# 8-electrovalvulas_V3.net
KiCad netlist of a schematic drawn in EAGLE
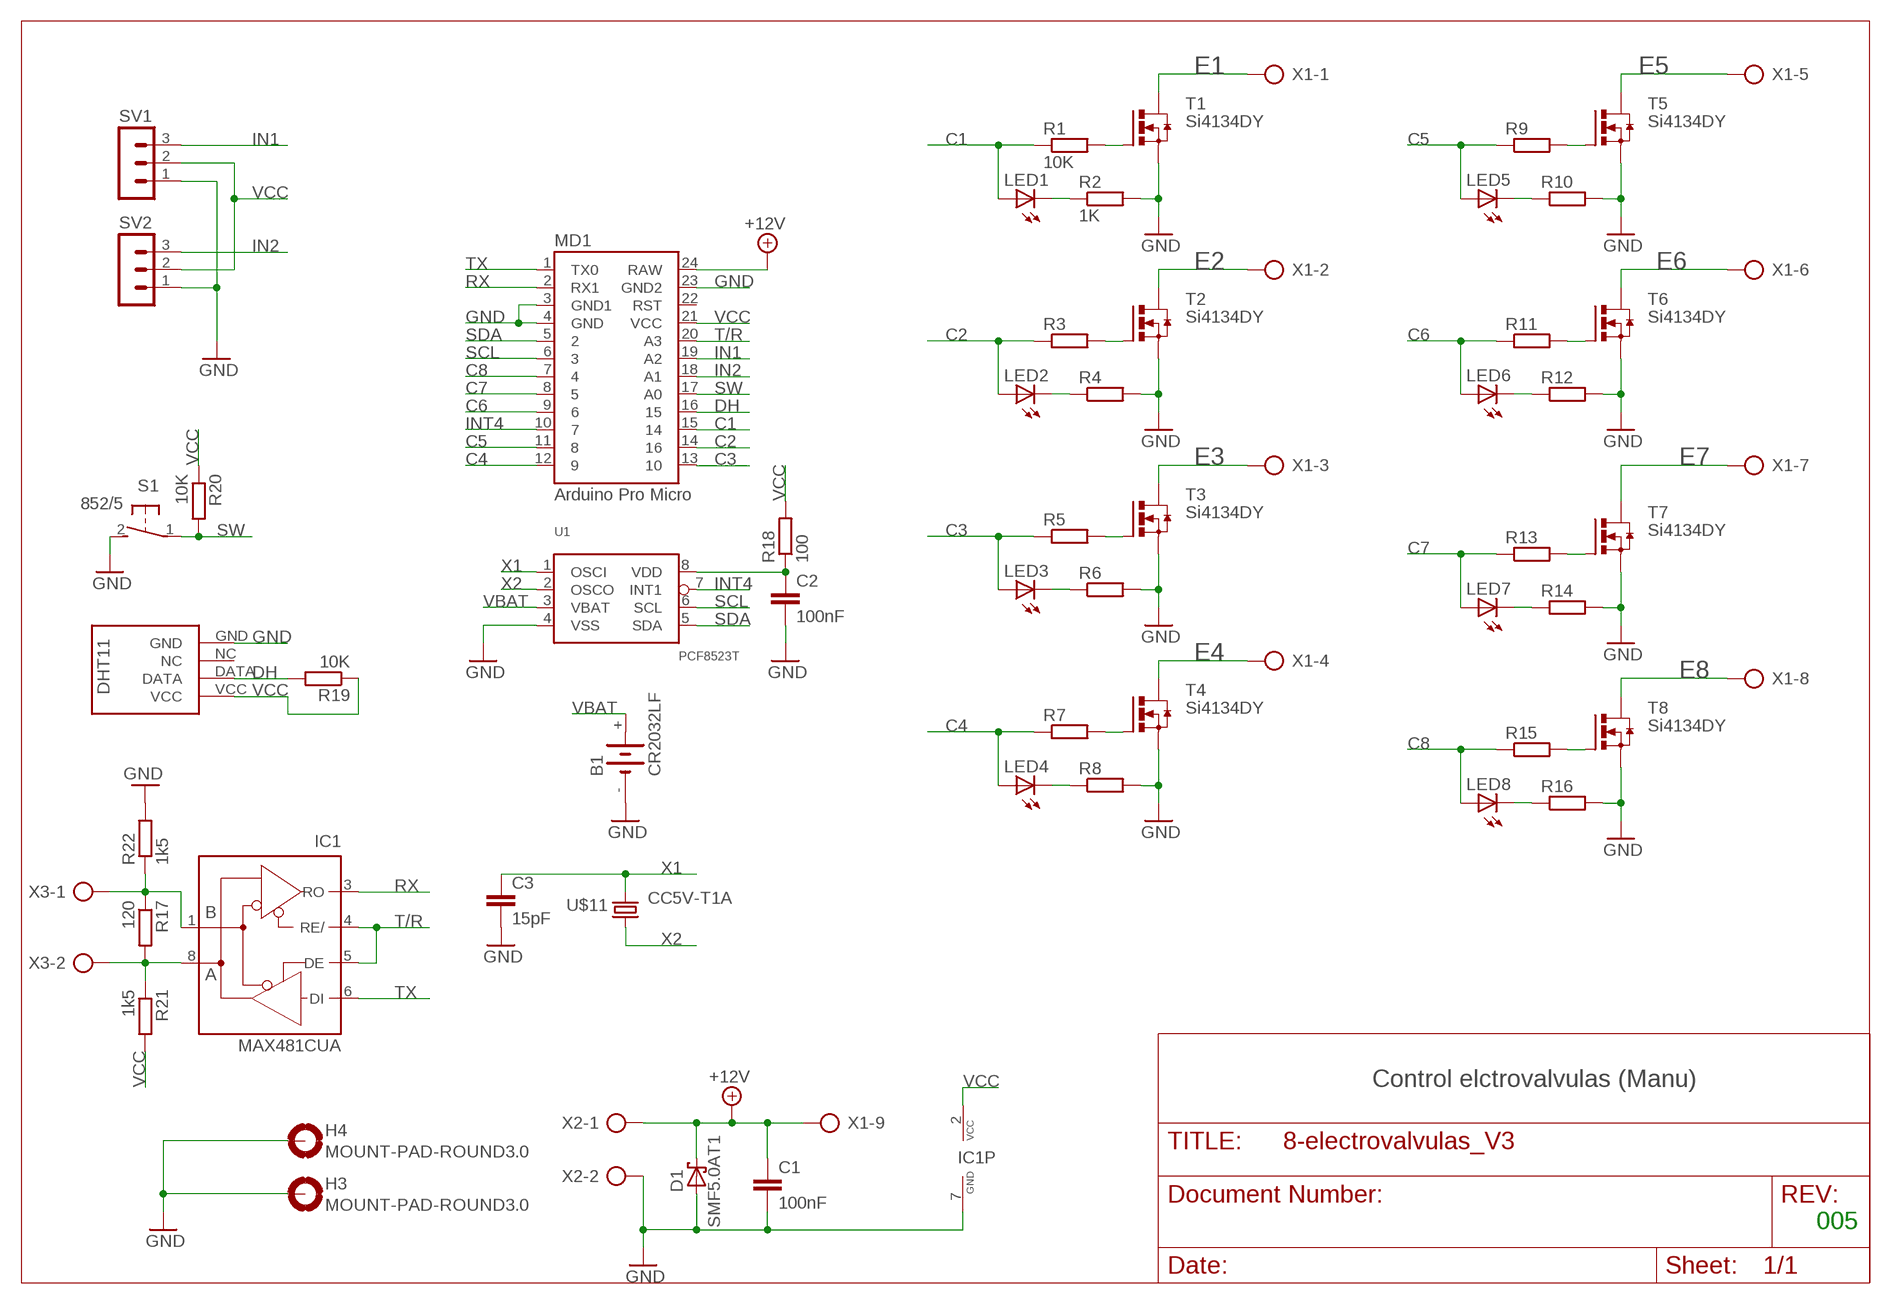
[diagram p0: schematic, sheet 1]

(export (version "E")
  (design (tool "Eeschema 10.0.6"))
  (components
    (comp (ref "B1")
      (value "CR2032LF")
      (footprint "eagle-import:BATTERY_1236_C")
      (libsource (lib "eagle-import") (part "BATTERY_2032LF"))
    )
    (comp (ref "C1")
      (value "100nF")
      (footprint "eagle-import:C1206")
      (libsource (lib "eagle-import") (part "C-EUC1206"))
    )
    (comp (ref "C2")
      (value "100nF")
      (footprint "eagle-import:C0603")
      (libsource (lib "eagle-import") (part "C-EUC0603"))
    )
    (comp (ref "C3")
      (value "15pF")
      (footprint "eagle-import:C0603")
      (libsource (lib "eagle-import") (part "C-EUC0603"))
    )
    (comp (ref "D1")
      (value "SMF5.0AT1")
      (footprint "eagle-import:SOD123FL")
      (libsource (lib "eagle-import") (part "SMF5.0AT1"))
    )
    (comp (ref "H3")
      (value "MOUNT-PAD-ROUND3.0")
      (footprint "eagle-import:3,0-PAD")
      (libsource (lib "eagle-import") (part "MOUNT-PAD-ROUND3.0"))
    )
    (comp (ref "H4")
      (value "MOUNT-PAD-ROUND3.0")
      (footprint "eagle-import:3,0-PAD")
      (libsource (lib "eagle-import") (part "MOUNT-PAD-ROUND3.0"))
    )
    (comp (ref "IC1")
      (value "MAX481CUA")
      (footprint "eagle-import:UMAX8")
      (fields (field (name "MPN") "MAX481CUA+"))
      (libsource (lib "eagle-import") (part "MAX481CUA"))
    )
    (comp (ref "IC10")
      (value "DHT11-PION.")
      (footprint "eagle-import:DHT11-PION.")
      (libsource (lib "eagle-import") (part "DHT11-PION."))
    )
    (comp (ref "LED1")
      (value "LEDSML0805")
      (footprint "eagle-import:SML0805")
      (libsource (lib "eagle-import") (part "LEDSML0805"))
    )
    (comp (ref "LED2")
      (value "LEDSML0805")
      (footprint "eagle-import:SML0805")
      (libsource (lib "eagle-import") (part "LEDSML0805"))
    )
    (comp (ref "LED3")
      (value "LEDSML0805")
      (footprint "eagle-import:SML0805")
      (libsource (lib "eagle-import") (part "LEDSML0805"))
    )
    (comp (ref "LED4")
      (value "LEDSML0805")
      (footprint "eagle-import:SML0805")
      (libsource (lib "eagle-import") (part "LEDSML0805"))
    )
    (comp (ref "LED5")
      (value "LEDSML0805")
      (footprint "eagle-import:SML0805")
      (libsource (lib "eagle-import") (part "LEDSML0805"))
    )
    (comp (ref "LED6")
      (value "LEDSML0805")
      (footprint "eagle-import:SML0805")
      (libsource (lib "eagle-import") (part "LEDSML0805"))
    )
    (comp (ref "LED7")
      (value "LEDSML0805")
      (footprint "eagle-import:SML0805")
      (libsource (lib "eagle-import") (part "LEDSML0805"))
    )
    (comp (ref "LED8")
      (value "LEDSML0805")
      (footprint "eagle-import:SML0805")
      (libsource (lib "eagle-import") (part "LEDSML0805"))
    )
    (comp (ref "MD1")
      (value "Arduino Pro Micro")
      (footprint "eagle-import:PRO_MICRO")
      (libsource (lib "eagle-import") (part "PRO_MICRO"))
    )
    (comp (ref "R1")
      (value "10K")
      (footprint "eagle-import:R0603")
      (libsource (lib "eagle-import") (part "R-EU_R0603"))
    )
    (comp (ref "R2")
      (value "1K")
      (footprint "eagle-import:R0603")
      (libsource (lib "eagle-import") (part "R-EU_R0603"))
    )
    (comp (ref "R3")
      (value "R-EU_R0603")
      (footprint "eagle-import:R0603")
      (libsource (lib "eagle-import") (part "R-EU_R0603"))
    )
    (comp (ref "R4")
      (value "R-EU_R0603")
      (footprint "eagle-import:R0603")
      (libsource (lib "eagle-import") (part "R-EU_R0603"))
    )
    (comp (ref "R5")
      (value "R-EU_R0603")
      (footprint "eagle-import:R0603")
      (libsource (lib "eagle-import") (part "R-EU_R0603"))
    )
    (comp (ref "R6")
      (value "R-EU_R0603")
      (footprint "eagle-import:R0603")
      (libsource (lib "eagle-import") (part "R-EU_R0603"))
    )
    (comp (ref "R7")
      (value "R-EU_R0603")
      (footprint "eagle-import:R0603")
      (libsource (lib "eagle-import") (part "R-EU_R0603"))
    )
    (comp (ref "R8")
      (value "R-EU_R0603")
      (footprint "eagle-import:R0603")
      (libsource (lib "eagle-import") (part "R-EU_R0603"))
    )
    (comp (ref "R9")
      (value "R-EU_R0603")
      (footprint "eagle-import:R0603")
      (libsource (lib "eagle-import") (part "R-EU_R0603"))
    )
    (comp (ref "R10")
      (value "R-EU_R0603")
      (footprint "eagle-import:R0603")
      (libsource (lib "eagle-import") (part "R-EU_R0603"))
    )
    (comp (ref "R11")
      (value "R-EU_R0603")
      (footprint "eagle-import:R0603")
      (libsource (lib "eagle-import") (part "R-EU_R0603"))
    )
    (comp (ref "R12")
      (value "R-EU_R0603")
      (footprint "eagle-import:R0603")
      (libsource (lib "eagle-import") (part "R-EU_R0603"))
    )
    (comp (ref "R13")
      (value "R-EU_R0603")
      (footprint "eagle-import:R0603")
      (libsource (lib "eagle-import") (part "R-EU_R0603"))
    )
    (comp (ref "R14")
      (value "R-EU_R0603")
      (footprint "eagle-import:R0603")
      (libsource (lib "eagle-import") (part "R-EU_R0603"))
    )
    (comp (ref "R15")
      (value "R-EU_R0603")
      (footprint "eagle-import:R0603")
      (libsource (lib "eagle-import") (part "R-EU_R0603"))
    )
    (comp (ref "R16")
      (value "R-EU_R0603")
      (footprint "eagle-import:R0603")
      (libsource (lib "eagle-import") (part "R-EU_R0603"))
    )
    (comp (ref "R17")
      (value "120")
      (footprint "eagle-import:R0603")
      (libsource (lib "eagle-import") (part "R-EU_R0603"))
    )
    (comp (ref "R18")
      (value "100")
      (footprint "eagle-import:R0603")
      (libsource (lib "eagle-import") (part "R-EU_R0603"))
    )
    (comp (ref "R19")
      (value "10K")
      (footprint "eagle-import:R0603")
      (libsource (lib "eagle-import") (part "R-EU_R0603"))
    )
    (comp (ref "R20")
      (value "10K")
      (footprint "eagle-import:R0603")
      (libsource (lib "eagle-import") (part "R-EU_R0603"))
    )
    (comp (ref "R21")
      (value "1k5")
      (footprint "eagle-import:R0603")
      (libsource (lib "eagle-import") (part "R-EU_R0603"))
    )
    (comp (ref "R22")
      (value "1k5")
      (footprint "eagle-import:R0603")
      (libsource (lib "eagle-import") (part "R-EU_R0603"))
    )
    (comp (ref "S1")
      (value "852/5")
      (footprint "eagle-import:B3F-31XX")
      (libsource (lib "eagle-import") (part "31-XX"))
    )
    (comp (ref "SV1")
      (value "MA03-1")
      (footprint "eagle-import:MA03-1")
      (libsource (lib "eagle-import") (part "MA03-1"))
    )
    (comp (ref "SV2")
      (value "MA03-1")
      (footprint "eagle-import:MA03-1")
      (libsource (lib "eagle-import") (part "MA03-1"))
    )
    (comp (ref "T1")
      (value "Si4134DY")
      (footprint "eagle-import:SO-08")
      (libsource (lib "eagle-import") (part "SI4134DY"))
    )
    (comp (ref "T2")
      (value "Si4134DY")
      (footprint "eagle-import:SO-08")
      (libsource (lib "eagle-import") (part "SI4134DY"))
    )
    (comp (ref "T3")
      (value "Si4134DY")
      (footprint "eagle-import:SO-08")
      (libsource (lib "eagle-import") (part "SI4134DY"))
    )
    (comp (ref "T4")
      (value "Si4134DY")
      (footprint "eagle-import:SO-08")
      (libsource (lib "eagle-import") (part "SI4134DY"))
    )
    (comp (ref "T5")
      (value "Si4134DY")
      (footprint "eagle-import:SO-08")
      (libsource (lib "eagle-import") (part "SI4134DY"))
    )
    (comp (ref "T6")
      (value "Si4134DY")
      (footprint "eagle-import:SO-08")
      (libsource (lib "eagle-import") (part "SI4134DY"))
    )
    (comp (ref "T7")
      (value "Si4134DY")
      (footprint "eagle-import:SO-08")
      (libsource (lib "eagle-import") (part "SI4134DY"))
    )
    (comp (ref "T8")
      (value "Si4134DY")
      (footprint "eagle-import:SO-08")
      (libsource (lib "eagle-import") (part "SI4134DY"))
    )
    (comp (ref "U$11")
      (value "CC5V-T1A")
      (footprint "eagle-import:T1A")
      (libsource (lib "eagle-import") (part "CC5V-T1A"))
    )
    (comp (ref "U1")
      (value "PCF8523T")
      (footprint "eagle-import:SOT96-1")
      (libsource (lib "eagle-import") (part "PCF8523T"))
    )
    (comp (ref "X1")
      (value "AK300/9")
      (footprint "eagle-import:AK300_9")
      (libsource (lib "eagle-import") (part "AK300/9"))
    )
    (comp (ref "X2")
      (value "AK300/2")
      (footprint "eagle-import:AK300_2")
      (libsource (lib "eagle-import") (part "AK300/2"))
    )
    (comp (ref "X3")
      (value "AK300/2")
      (footprint "eagle-import:AK300_2")
      (libsource (lib "eagle-import") (part "AK300/2"))
    )
  )
  (nets
    (net (code "1") (name "+12V") (class "Default")
      (node (ref "C1") (pin "1") (pinfunction "1_1") (pintype "passive"))
      (node (ref "D1") (pin "C") (pinfunction "C_C") (pintype "passive"))
      (node (ref "MD1") (pin "24") (pinfunction "RAW_24") (pintype "bidirectional"))
      (node (ref "X1") (pin "9") (pinfunction "KL_9") (pintype "passive"))
      (node (ref "X2") (pin "1") (pinfunction "KL_1") (pintype "passive"))
    )
    (net (code "2") (name "/C1") (class "Default")
      (node (ref "LED1") (pin "A") (pinfunction "A_A") (pintype "passive"))
      (node (ref "MD1") (pin "15") (pinfunction "14_15") (pintype "bidirectional"))
      (node (ref "R1") (pin "1") (pinfunction "1_1") (pintype "passive"))
    )
    (net (code "3") (name "/C2") (class "Default")
      (node (ref "LED2") (pin "A") (pinfunction "A_A") (pintype "passive"))
      (node (ref "MD1") (pin "14") (pinfunction "16_14") (pintype "bidirectional"))
      (node (ref "R3") (pin "1") (pinfunction "1_1") (pintype "passive"))
    )
    (net (code "4") (name "/C3") (class "Default")
      (node (ref "LED3") (pin "A") (pinfunction "A_A") (pintype "passive"))
      (node (ref "MD1") (pin "13") (pinfunction "10_13") (pintype "bidirectional"))
      (node (ref "R5") (pin "1") (pinfunction "1_1") (pintype "passive"))
    )
    (net (code "5") (name "/C4") (class "Default")
      (node (ref "LED4") (pin "A") (pinfunction "A_A") (pintype "passive"))
      (node (ref "MD1") (pin "12") (pinfunction "9_12") (pintype "bidirectional"))
      (node (ref "R7") (pin "1") (pinfunction "1_1") (pintype "passive"))
    )
    (net (code "6") (name "/C5") (class "Default")
      (node (ref "LED5") (pin "A") (pinfunction "A_A") (pintype "passive"))
      (node (ref "MD1") (pin "11") (pinfunction "8_11") (pintype "bidirectional"))
      (node (ref "R9") (pin "1") (pinfunction "1_1") (pintype "passive"))
    )
    (net (code "7") (name "/C6") (class "Default")
      (node (ref "LED6") (pin "A") (pinfunction "A_A") (pintype "passive"))
      (node (ref "MD1") (pin "9") (pinfunction "6_9") (pintype "bidirectional"))
      (node (ref "R11") (pin "1") (pinfunction "1_1") (pintype "passive"))
    )
    (net (code "8") (name "/C7") (class "Default")
      (node (ref "LED7") (pin "A") (pinfunction "A_A") (pintype "passive"))
      (node (ref "MD1") (pin "8") (pinfunction "5_8") (pintype "bidirectional"))
      (node (ref "R13") (pin "1") (pinfunction "1_1") (pintype "passive"))
    )
    (net (code "9") (name "/C8") (class "Default")
      (node (ref "LED8") (pin "A") (pinfunction "A_A") (pintype "passive"))
      (node (ref "MD1") (pin "7") (pinfunction "4_7") (pintype "bidirectional"))
      (node (ref "R15") (pin "1") (pinfunction "1_1") (pintype "passive"))
    )
    (net (code "10") (name "/DH") (class "Default")
      (node (ref "IC10") (pin "DATA") (pinfunction "DATA_DATA") (pintype "bidirectional"))
      (node (ref "MD1") (pin "16") (pinfunction "15_16") (pintype "bidirectional"))
      (node (ref "R19") (pin "2") (pinfunction "2_2") (pintype "passive"))
    )
    (net (code "11") (name "/E1") (class "Default")
      (node (ref "T1") (pin "5") (pinfunction "D_5") (pintype "passive"))
      (node (ref "T1") (pin "6") (pinfunction "D_6") (pintype "passive"))
      (node (ref "T1") (pin "7") (pinfunction "D_7") (pintype "passive"))
      (node (ref "T1") (pin "8") (pinfunction "D_8") (pintype "passive"))
      (node (ref "X1") (pin "1") (pinfunction "KL_1") (pintype "passive"))
    )
    (net (code "12") (name "/E2") (class "Default")
      (node (ref "T2") (pin "5") (pinfunction "D_5") (pintype "passive"))
      (node (ref "T2") (pin "6") (pinfunction "D_6") (pintype "passive"))
      (node (ref "T2") (pin "7") (pinfunction "D_7") (pintype "passive"))
      (node (ref "T2") (pin "8") (pinfunction "D_8") (pintype "passive"))
      (node (ref "X1") (pin "2") (pinfunction "KL_2") (pintype "passive"))
    )
    (net (code "13") (name "/E3") (class "Default")
      (node (ref "T3") (pin "5") (pinfunction "D_5") (pintype "passive"))
      (node (ref "T3") (pin "6") (pinfunction "D_6") (pintype "passive"))
      (node (ref "T3") (pin "7") (pinfunction "D_7") (pintype "passive"))
      (node (ref "T3") (pin "8") (pinfunction "D_8") (pintype "passive"))
      (node (ref "X1") (pin "3") (pinfunction "KL_3") (pintype "passive"))
    )
    (net (code "14") (name "/E4") (class "Default")
      (node (ref "T4") (pin "5") (pinfunction "D_5") (pintype "passive"))
      (node (ref "T4") (pin "6") (pinfunction "D_6") (pintype "passive"))
      (node (ref "T4") (pin "7") (pinfunction "D_7") (pintype "passive"))
      (node (ref "T4") (pin "8") (pinfunction "D_8") (pintype "passive"))
      (node (ref "X1") (pin "4") (pinfunction "KL_4") (pintype "passive"))
    )
    (net (code "15") (name "/E5") (class "Default")
      (node (ref "T5") (pin "5") (pinfunction "D_5") (pintype "passive"))
      (node (ref "T5") (pin "6") (pinfunction "D_6") (pintype "passive"))
      (node (ref "T5") (pin "7") (pinfunction "D_7") (pintype "passive"))
      (node (ref "T5") (pin "8") (pinfunction "D_8") (pintype "passive"))
      (node (ref "X1") (pin "5") (pinfunction "KL_5") (pintype "passive"))
    )
    (net (code "16") (name "/E6") (class "Default")
      (node (ref "T6") (pin "5") (pinfunction "D_5") (pintype "passive"))
      (node (ref "T6") (pin "6") (pinfunction "D_6") (pintype "passive"))
      (node (ref "T6") (pin "7") (pinfunction "D_7") (pintype "passive"))
      (node (ref "T6") (pin "8") (pinfunction "D_8") (pintype "passive"))
      (node (ref "X1") (pin "6") (pinfunction "KL_6") (pintype "passive"))
    )
    (net (code "17") (name "/E7") (class "Default")
      (node (ref "T7") (pin "5") (pinfunction "D_5") (pintype "passive"))
      (node (ref "T7") (pin "6") (pinfunction "D_6") (pintype "passive"))
      (node (ref "T7") (pin "7") (pinfunction "D_7") (pintype "passive"))
      (node (ref "T7") (pin "8") (pinfunction "D_8") (pintype "passive"))
      (node (ref "X1") (pin "7") (pinfunction "KL_7") (pintype "passive"))
    )
    (net (code "18") (name "/E8") (class "Default")
      (node (ref "T8") (pin "5") (pinfunction "D_5") (pintype "passive"))
      (node (ref "T8") (pin "6") (pinfunction "D_6") (pintype "passive"))
      (node (ref "T8") (pin "7") (pinfunction "D_7") (pintype "passive"))
      (node (ref "T8") (pin "8") (pinfunction "D_8") (pintype "passive"))
      (node (ref "X1") (pin "8") (pinfunction "KL_8") (pintype "passive"))
    )
    (net (code "19") (name "/IN1") (class "Default")
      (node (ref "MD1") (pin "19") (pinfunction "A2_19") (pintype "bidirectional"))
      (node (ref "SV1") (pin "3") (pinfunction "3_3") (pintype "passive"))
    )
    (net (code "20") (name "/IN2") (class "Default")
      (node (ref "MD1") (pin "18") (pinfunction "A1_18") (pintype "bidirectional"))
      (node (ref "SV2") (pin "3") (pinfunction "3_3") (pintype "passive"))
    )
    (net (code "21") (name "/INT4") (class "Default")
      (node (ref "MD1") (pin "10") (pinfunction "7_10") (pintype "bidirectional"))
      (node (ref "U1") (pin "7") (pinfunction "INT1_7") (pintype "output"))
    )
    (net (code "22") (name "/RX") (class "Default")
      (node (ref "IC1") (pin "3") (pinfunction "RO_3") (pintype "output"))
      (node (ref "MD1") (pin "2") (pinfunction "RX1_2") (pintype "bidirectional"))
    )
    (net (code "23") (name "/SCL") (class "Default")
      (node (ref "MD1") (pin "6") (pinfunction "3_6") (pintype "bidirectional"))
      (node (ref "U1") (pin "6") (pinfunction "SCL_6") (pintype "input"))
    )
    (net (code "24") (name "/SDA") (class "Default")
      (node (ref "MD1") (pin "5") (pinfunction "2_5") (pintype "bidirectional"))
      (node (ref "U1") (pin "5") (pinfunction "SDA_5") (pintype "bidirectional"))
    )
    (net (code "25") (name "/SW") (class "Default")
      (node (ref "MD1") (pin "17") (pinfunction "A0_17") (pintype "bidirectional"))
      (node (ref "R20") (pin "2") (pinfunction "2_2") (pintype "passive"))
      (node (ref "S1") (pin "1") (pinfunction "P_1") (pintype "passive"))
    )
    (net (code "26") (name "/TX") (class "Default")
      (node (ref "IC1") (pin "6") (pinfunction "DI_6") (pintype "input"))
      (node (ref "MD1") (pin "1") (pinfunction "TX0_1") (pintype "bidirectional"))
    )
    (net (code "27") (name "/T{slash}R") (class "Default")
      (node (ref "IC1") (pin "4") (pinfunction "RE/_4") (pintype "input"))
      (node (ref "IC1") (pin "5") (pinfunction "DE_5") (pintype "input"))
      (node (ref "MD1") (pin "20") (pinfunction "A3_20") (pintype "bidirectional"))
    )
    (net (code "28") (name "/VBAT") (class "Default")
      (node (ref "B1") (pin "+") (pinfunction "+_+") (pintype "passive"))
      (node (ref "U1") (pin "3") (pinfunction "VBAT_3") (pintype "power_in"))
    )
    (net (code "29") (name "/VCC") (class "Default")
      (node (ref "IC1") (pin "2") (pinfunction "VCC_2") (pintype "power_in"))
      (node (ref "IC10") (pin "VCC") (pinfunction "VCC_VCC") (pintype "bidirectional"))
      (node (ref "MD1") (pin "21") (pinfunction "VCC_21") (pintype "bidirectional"))
      (node (ref "R18") (pin "2") (pinfunction "2_2") (pintype "passive"))
      (node (ref "R19") (pin "1") (pinfunction "1_1") (pintype "passive"))
      (node (ref "R20") (pin "1") (pinfunction "1_1") (pintype "passive"))
      (node (ref "R21") (pin "2") (pinfunction "2_2") (pintype "passive"))
      (node (ref "SV1") (pin "2") (pinfunction "2_2") (pintype "passive"))
      (node (ref "SV2") (pin "2") (pinfunction "2_2") (pintype "passive"))
    )
    (net (code "30") (name "/X1") (class "Default")
      (node (ref "C3") (pin "1") (pinfunction "1_1") (pintype "passive"))
      (node (ref "U$11") (pin "2") (pinfunction "2_2") (pintype "passive"))
      (node (ref "U1") (pin "1") (pinfunction "OSCI_1") (pintype "passive"))
    )
    (net (code "31") (name "/X2") (class "Default")
      (node (ref "U$11") (pin "1") (pinfunction "1_1") (pintype "passive"))
      (node (ref "U1") (pin "2") (pinfunction "OSCO_2") (pintype "passive"))
    )
    (net (code "32") (name "GND") (class "Default")
      (node (ref "B1") (pin "-") (pinfunction "-_-") (pintype "passive"))
      (node (ref "C1") (pin "2") (pinfunction "2_2") (pintype "passive"))
      (node (ref "C2") (pin "2") (pinfunction "2_2") (pintype "passive"))
      (node (ref "C3") (pin "2") (pinfunction "2_2") (pintype "passive"))
      (node (ref "D1") (pin "A") (pinfunction "A_A") (pintype "passive"))
      (node (ref "H3") (pin "B3,0") (pinfunction "MOUNT_B3,0") (pintype "passive"))
      (node (ref "H4") (pin "B3,0") (pinfunction "MOUNT_B3,0") (pintype "passive"))
      (node (ref "IC1") (pin "7") (pinfunction "GND_7") (pintype "power_in"))
      (node (ref "IC10") (pin "GND") (pinfunction "GND_GND") (pintype "bidirectional"))
      (node (ref "MD1") (pin "23") (pinfunction "GND2_23") (pintype "bidirectional"))
      (node (ref "MD1") (pin "3") (pinfunction "GND1_3") (pintype "bidirectional"))
      (node (ref "MD1") (pin "4") (pinfunction "GND_4") (pintype "bidirectional"))
      (node (ref "R10") (pin "2") (pinfunction "2_2") (pintype "passive"))
      (node (ref "R12") (pin "2") (pinfunction "2_2") (pintype "passive"))
      (node (ref "R14") (pin "2") (pinfunction "2_2") (pintype "passive"))
      (node (ref "R16") (pin "2") (pinfunction "2_2") (pintype "passive"))
      (node (ref "R2") (pin "2") (pinfunction "2_2") (pintype "passive"))
      (node (ref "R22") (pin "2") (pinfunction "2_2") (pintype "passive"))
      (node (ref "R4") (pin "2") (pinfunction "2_2") (pintype "passive"))
      (node (ref "R6") (pin "2") (pinfunction "2_2") (pintype "passive"))
      (node (ref "R8") (pin "2") (pinfunction "2_2") (pintype "passive"))
      (node (ref "S1") (pin "2") (pinfunction "S_2") (pintype "passive"))
      (node (ref "SV1") (pin "1") (pinfunction "1_1") (pintype "passive"))
      (node (ref "SV2") (pin "1") (pinfunction "1_1") (pintype "passive"))
      (node (ref "T1") (pin "1") (pinfunction "S_1") (pintype "passive"))
      (node (ref "T1") (pin "2") (pinfunction "S_2") (pintype "passive"))
      (node (ref "T1") (pin "3") (pinfunction "S_3") (pintype "passive"))
      (node (ref "T2") (pin "1") (pinfunction "S_1") (pintype "passive"))
      (node (ref "T2") (pin "2") (pinfunction "S_2") (pintype "passive"))
      (node (ref "T2") (pin "3") (pinfunction "S_3") (pintype "passive"))
      (node (ref "T3") (pin "1") (pinfunction "S_1") (pintype "passive"))
      (node (ref "T3") (pin "2") (pinfunction "S_2") (pintype "passive"))
      (node (ref "T3") (pin "3") (pinfunction "S_3") (pintype "passive"))
      (node (ref "T4") (pin "1") (pinfunction "S_1") (pintype "passive"))
      (node (ref "T4") (pin "2") (pinfunction "S_2") (pintype "passive"))
      (node (ref "T4") (pin "3") (pinfunction "S_3") (pintype "passive"))
      (node (ref "T5") (pin "1") (pinfunction "S_1") (pintype "passive"))
      (node (ref "T5") (pin "2") (pinfunction "S_2") (pintype "passive"))
      (node (ref "T5") (pin "3") (pinfunction "S_3") (pintype "passive"))
      (node (ref "T6") (pin "1") (pinfunction "S_1") (pintype "passive"))
      (node (ref "T6") (pin "2") (pinfunction "S_2") (pintype "passive"))
      (node (ref "T6") (pin "3") (pinfunction "S_3") (pintype "passive"))
      (node (ref "T7") (pin "1") (pinfunction "S_1") (pintype "passive"))
      (node (ref "T7") (pin "2") (pinfunction "S_2") (pintype "passive"))
      (node (ref "T7") (pin "3") (pinfunction "S_3") (pintype "passive"))
      (node (ref "T8") (pin "1") (pinfunction "S_1") (pintype "passive"))
      (node (ref "T8") (pin "2") (pinfunction "S_2") (pintype "passive"))
      (node (ref "T8") (pin "3") (pinfunction "S_3") (pintype "passive"))
      (node (ref "U1") (pin "4") (pinfunction "VSS_4") (pintype "power_in"))
      (node (ref "X2") (pin "2") (pinfunction "KL_2") (pintype "passive"))
    )
    (net (code "33") (name "Net-(IC1A-A)") (class "Default")
      (node (ref "IC1") (pin "8") (pinfunction "A_8") (pintype "passive"))
      (node (ref "R17") (pin "2") (pinfunction "2_2") (pintype "passive"))
      (node (ref "R21") (pin "1") (pinfunction "1_1") (pintype "passive"))
      (node (ref "X3") (pin "2") (pinfunction "KL_2") (pintype "passive"))
    )
    (net (code "34") (name "Net-(IC1A-B)") (class "Default")
      (node (ref "IC1") (pin "1") (pinfunction "B_1") (pintype "passive"))
      (node (ref "R17") (pin "1") (pinfunction "1_1") (pintype "passive"))
      (node (ref "R22") (pin "1") (pinfunction "1_1") (pintype "passive"))
      (node (ref "X3") (pin "1") (pinfunction "KL_1") (pintype "passive"))
    )
    (net (code "35") (name "Net-(LED1-PadC)") (class "Default")
      (node (ref "LED1") (pin "C") (pinfunction "C_C") (pintype "passive"))
      (node (ref "R2") (pin "1") (pinfunction "1_1") (pintype "passive"))
    )
    (net (code "36") (name "Net-(LED2-PadC)") (class "Default")
      (node (ref "LED2") (pin "C") (pinfunction "C_C") (pintype "passive"))
      (node (ref "R4") (pin "1") (pinfunction "1_1") (pintype "passive"))
    )
    (net (code "37") (name "Net-(LED3-PadC)") (class "Default")
      (node (ref "LED3") (pin "C") (pinfunction "C_C") (pintype "passive"))
      (node (ref "R6") (pin "1") (pinfunction "1_1") (pintype "passive"))
    )
    (net (code "38") (name "Net-(LED4-PadC)") (class "Default")
      (node (ref "LED4") (pin "C") (pinfunction "C_C") (pintype "passive"))
      (node (ref "R8") (pin "1") (pinfunction "1_1") (pintype "passive"))
    )
    (net (code "39") (name "Net-(LED5-PadC)") (class "Default")
      (node (ref "LED5") (pin "C") (pinfunction "C_C") (pintype "passive"))
      (node (ref "R10") (pin "1") (pinfunction "1_1") (pintype "passive"))
    )
    (net (code "40") (name "Net-(LED6-PadC)") (class "Default")
      (node (ref "LED6") (pin "C") (pinfunction "C_C") (pintype "passive"))
      (node (ref "R12") (pin "1") (pinfunction "1_1") (pintype "passive"))
    )
    (net (code "41") (name "Net-(LED7-PadC)") (class "Default")
      (node (ref "LED7") (pin "C") (pinfunction "C_C") (pintype "passive"))
      (node (ref "R14") (pin "1") (pinfunction "1_1") (pintype "passive"))
    )
    (net (code "42") (name "Net-(LED8-PadC)") (class "Default")
      (node (ref "LED8") (pin "C") (pinfunction "C_C") (pintype "passive"))
      (node (ref "R16") (pin "1") (pinfunction "1_1") (pintype "passive"))
    )
    (net (code "43") (name "Net-(T1-G)") (class "Default")
      (node (ref "R1") (pin "2") (pinfunction "2_2") (pintype "passive"))
      (node (ref "T1") (pin "4") (pinfunction "G_4") (pintype "passive"))
    )
    (net (code "44") (name "Net-(T2-G)") (class "Default")
      (node (ref "R3") (pin "2") (pinfunction "2_2") (pintype "passive"))
      (node (ref "T2") (pin "4") (pinfunction "G_4") (pintype "passive"))
    )
    (net (code "45") (name "Net-(T3-G)") (class "Default")
      (node (ref "R5") (pin "2") (pinfunction "2_2") (pintype "passive"))
      (node (ref "T3") (pin "4") (pinfunction "G_4") (pintype "passive"))
    )
    (net (code "46") (name "Net-(T4-G)") (class "Default")
      (node (ref "R7") (pin "2") (pinfunction "2_2") (pintype "passive"))
      (node (ref "T4") (pin "4") (pinfunction "G_4") (pintype "passive"))
    )
    (net (code "47") (name "Net-(T5-G)") (class "Default")
      (node (ref "R9") (pin "2") (pinfunction "2_2") (pintype "passive"))
      (node (ref "T5") (pin "4") (pinfunction "G_4") (pintype "passive"))
    )
    (net (code "48") (name "Net-(T6-G)") (class "Default")
      (node (ref "R11") (pin "2") (pinfunction "2_2") (pintype "passive"))
      (node (ref "T6") (pin "4") (pinfunction "G_4") (pintype "passive"))
    )
    (net (code "49") (name "Net-(T7-G)") (class "Default")
      (node (ref "R13") (pin "2") (pinfunction "2_2") (pintype "passive"))
      (node (ref "T7") (pin "4") (pinfunction "G_4") (pintype "passive"))
    )
    (net (code "50") (name "Net-(T8-G)") (class "Default")
      (node (ref "R15") (pin "2") (pinfunction "2_2") (pintype "passive"))
      (node (ref "T8") (pin "4") (pinfunction "G_4") (pintype "passive"))
    )
    (net (code "51") (name "Net-(U1-VDD)") (class "Default")
      (node (ref "C2") (pin "1") (pinfunction "1_1") (pintype "passive"))
      (node (ref "R18") (pin "1") (pinfunction "1_1") (pintype "passive"))
      (node (ref "U1") (pin "8") (pinfunction "VDD_8") (pintype "power_in"))
    )
    (net (code "52") (name "unconnected-(IC10-PadNC)") (class "Default")
      (node (ref "IC10") (pin "NC") (pinfunction "NC_NC") (pintype "bidirectional"))
    )
    (net (code "53") (name "unconnected-(MD1-RST-Pad22)") (class "Default")
      (node (ref "MD1") (pin "22") (pinfunction "RST_22") (pintype "bidirectional"))
    )
  )
)
